# 2_viper_eagle_rep-matrix.net
KiCad netlist of a schematic drawn in Altium Designer
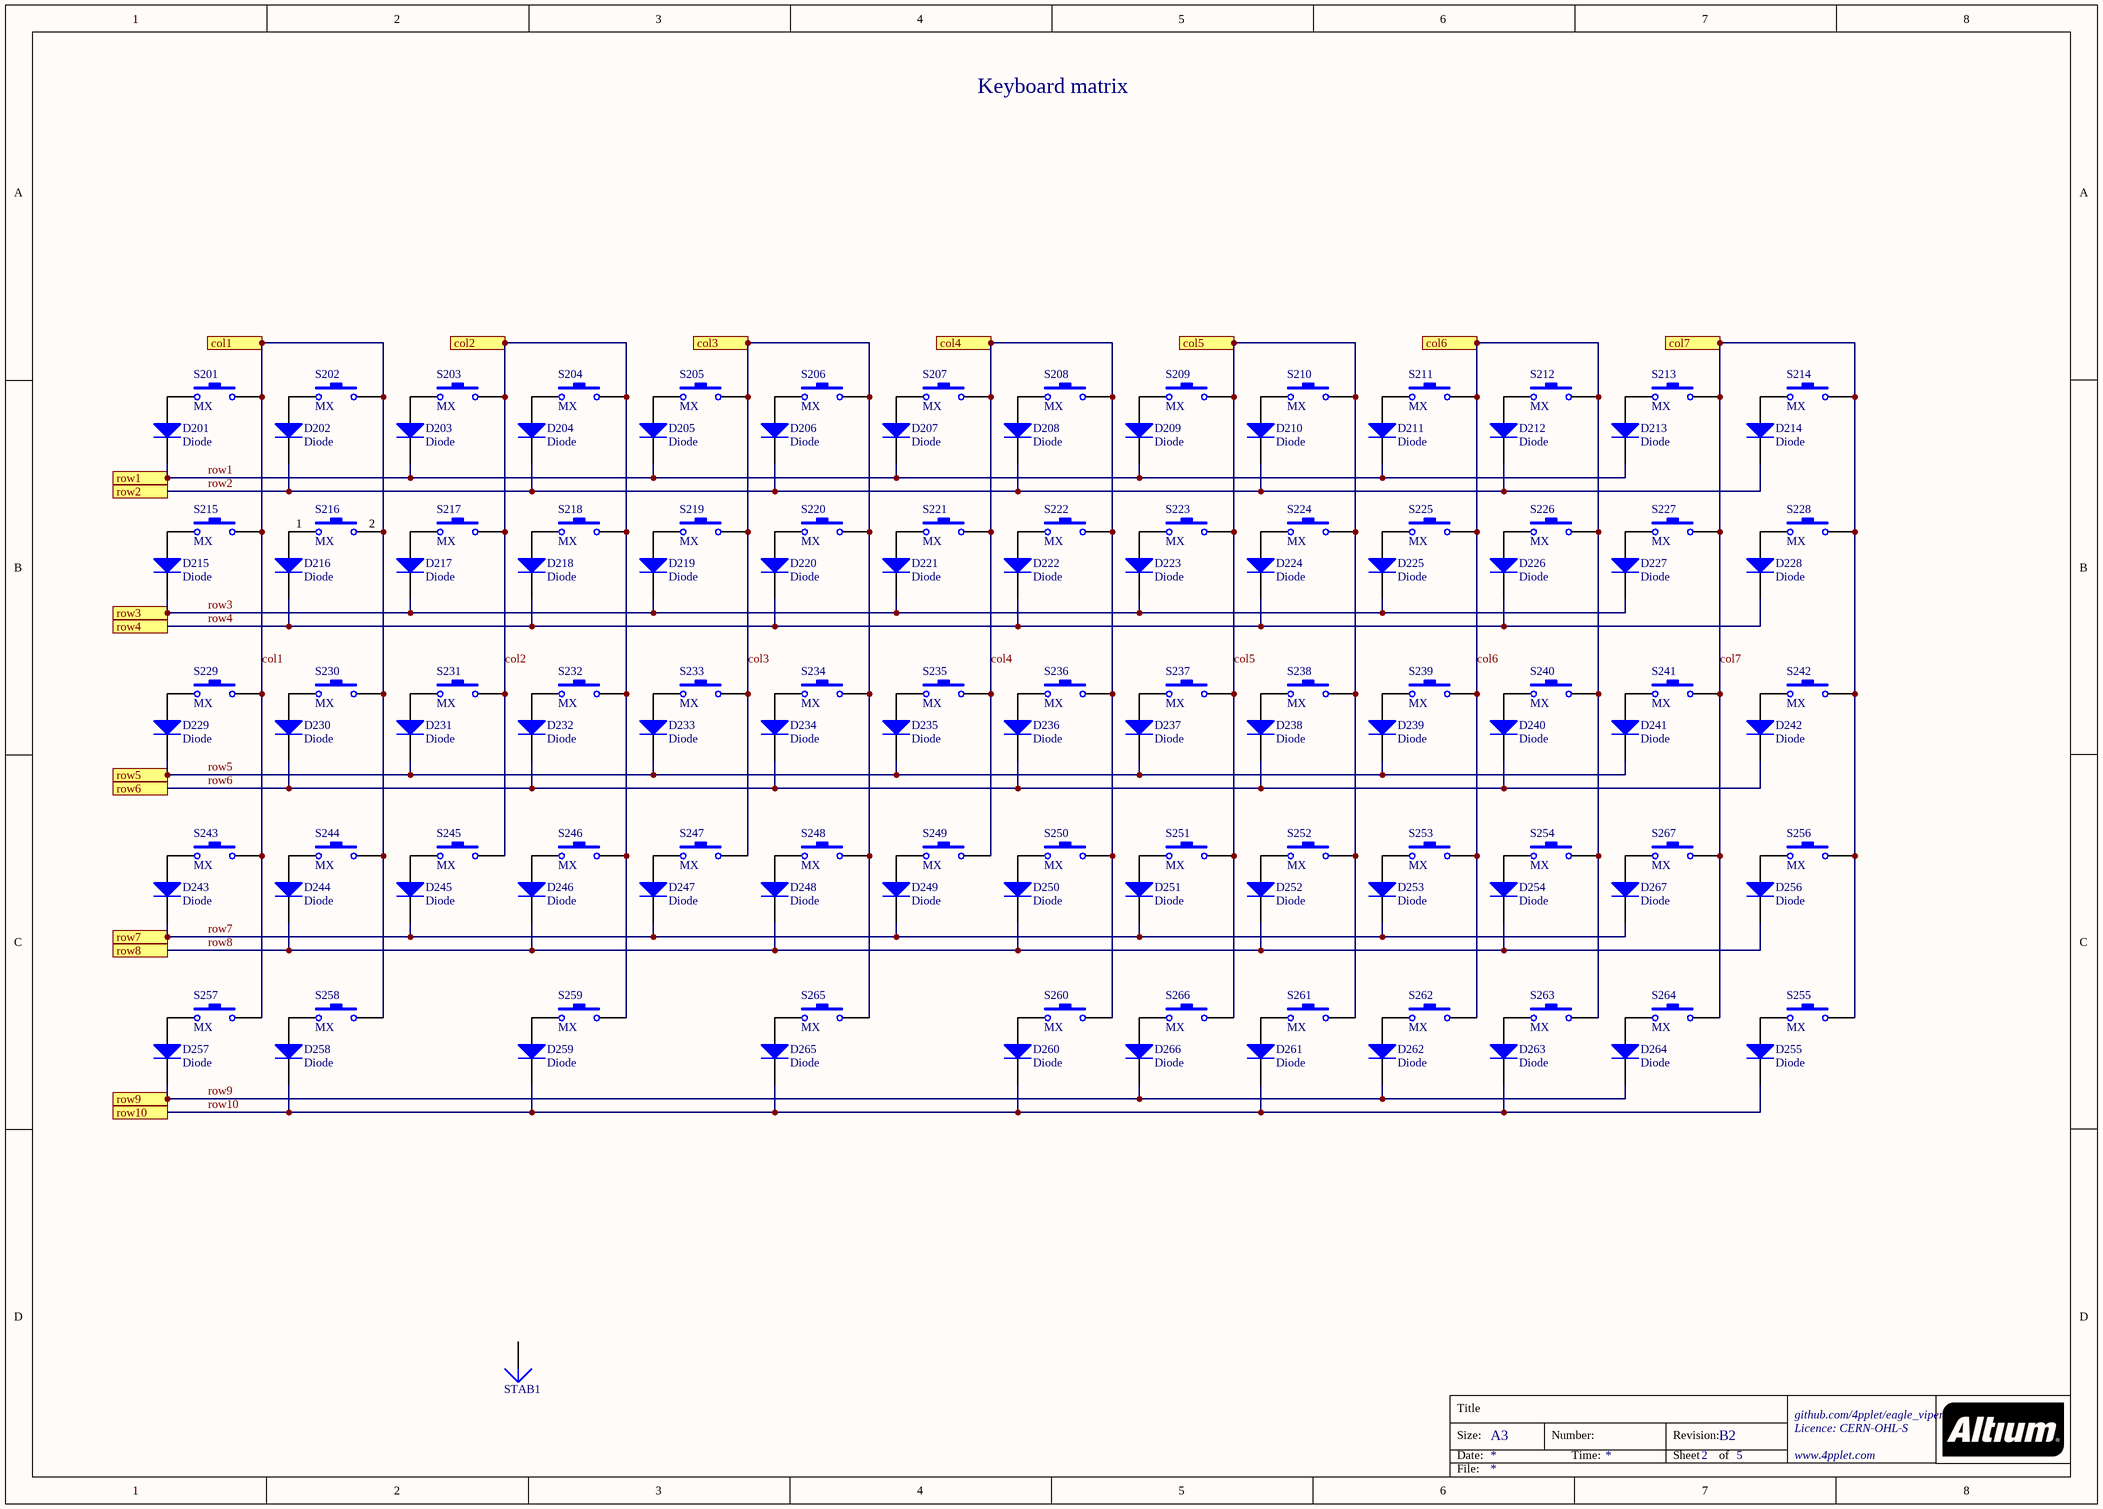
[diagram p0: 2_viper_eagle_rep-matrix.SchDoc]

(export (version "E")
  (design (tool "Eeschema 10.0.6"))
  (components
    (comp (ref "D201")
      (value "Diode")
      (footprint "SOD-123")
      (description "Default Diode")
      (fields (field (name "LCSC PART #") "C81598") (field (name "MRF.PART") "1N4148W"))
      (libsource (lib "Miscellaneous Devices") (part "Diode"))
    )
    (comp (ref "D202")
      (value "Diode")
      (footprint "SOD-123")
      (description "Default Diode")
      (fields (field (name "LCSC PART #") "C81598") (field (name "MRF.PART") "1N4148W"))
      (libsource (lib "Miscellaneous Devices") (part "Diode"))
    )
    (comp (ref "D203")
      (value "Diode")
      (footprint "SOD-123")
      (description "Default Diode")
      (fields (field (name "LCSC PART #") "C81598") (field (name "MRF.PART") "1N4148W"))
      (libsource (lib "Miscellaneous Devices") (part "Diode"))
    )
    (comp (ref "D204")
      (value "Diode")
      (footprint "SOD-123")
      (description "Default Diode")
      (fields (field (name "LCSC PART #") "C81598") (field (name "MRF.PART") "1N4148W"))
      (libsource (lib "Miscellaneous Devices") (part "Diode"))
    )
    (comp (ref "D205")
      (value "Diode")
      (footprint "SOD-123")
      (description "Default Diode")
      (fields (field (name "LCSC PART #") "C81598") (field (name "MRF.PART") "1N4148W"))
      (libsource (lib "Miscellaneous Devices") (part "Diode"))
    )
    (comp (ref "D206")
      (value "Diode")
      (footprint "SOD-123")
      (description "Default Diode")
      (fields (field (name "LCSC PART #") "C81598") (field (name "MRF.PART") "1N4148W"))
      (libsource (lib "Miscellaneous Devices") (part "Diode"))
    )
    (comp (ref "D207")
      (value "Diode")
      (footprint "SOD-123")
      (description "Default Diode")
      (fields (field (name "LCSC PART #") "C81598") (field (name "MRF.PART") "1N4148W"))
      (libsource (lib "Miscellaneous Devices") (part "Diode"))
    )
    (comp (ref "D208")
      (value "Diode")
      (footprint "SOD-123")
      (description "Default Diode")
      (fields (field (name "LCSC PART #") "C81598") (field (name "MRF.PART") "1N4148W"))
      (libsource (lib "Miscellaneous Devices") (part "Diode"))
    )
    (comp (ref "D209")
      (value "Diode")
      (footprint "SOD-123")
      (description "Default Diode")
      (fields (field (name "LCSC PART #") "C81598") (field (name "MRF.PART") "1N4148W"))
      (libsource (lib "Miscellaneous Devices") (part "Diode"))
    )
    (comp (ref "D210")
      (value "Diode")
      (footprint "SOD-123")
      (description "Default Diode")
      (fields (field (name "LCSC PART #") "C81598") (field (name "MRF.PART") "1N4148W"))
      (libsource (lib "Miscellaneous Devices") (part "Diode"))
    )
    (comp (ref "D211")
      (value "Diode")
      (footprint "SOD-123")
      (description "Default Diode")
      (fields (field (name "LCSC PART #") "C81598") (field (name "MRF.PART") "1N4148W"))
      (libsource (lib "Miscellaneous Devices") (part "Diode"))
    )
    (comp (ref "D212")
      (value "Diode")
      (footprint "SOD-123")
      (description "Default Diode")
      (fields (field (name "LCSC PART #") "C81598") (field (name "MRF.PART") "1N4148W"))
      (libsource (lib "Miscellaneous Devices") (part "Diode"))
    )
    (comp (ref "D213")
      (value "Diode")
      (footprint "SOD-123")
      (description "Default Diode")
      (fields (field (name "LCSC PART #") "C81598") (field (name "MRF.PART") "1N4148W"))
      (libsource (lib "Miscellaneous Devices") (part "Diode"))
    )
    (comp (ref "D214")
      (value "Diode")
      (footprint "SOD-123")
      (description "Default Diode")
      (fields (field (name "LCSC PART #") "C81598") (field (name "MRF.PART") "1N4148W"))
      (libsource (lib "Miscellaneous Devices") (part "Diode"))
    )
    (comp (ref "D215")
      (value "Diode")
      (footprint "SOD-123")
      (description "Default Diode")
      (fields (field (name "LCSC PART #") "C81598") (field (name "MRF.PART") "1N4148W"))
      (libsource (lib "Miscellaneous Devices") (part "Diode"))
    )
    (comp (ref "D216")
      (value "Diode")
      (footprint "SOD-123")
      (description "Default Diode")
      (fields (field (name "LCSC PART #") "C81598") (field (name "MRF.PART") "1N4148W"))
      (libsource (lib "Miscellaneous Devices") (part "Diode"))
    )
    (comp (ref "D217")
      (value "Diode")
      (footprint "SOD-123")
      (description "Default Diode")
      (fields (field (name "LCSC PART #") "C81598") (field (name "MRF.PART") "1N4148W"))
      (libsource (lib "Miscellaneous Devices") (part "Diode"))
    )
    (comp (ref "D218")
      (value "Diode")
      (footprint "SOD-123")
      (description "Default Diode")
      (fields (field (name "LCSC PART #") "C81598") (field (name "MRF.PART") "1N4148W"))
      (libsource (lib "Miscellaneous Devices") (part "Diode"))
    )
    (comp (ref "D219")
      (value "Diode")
      (footprint "SOD-123")
      (description "Default Diode")
      (fields (field (name "LCSC PART #") "C81598") (field (name "MRF.PART") "1N4148W"))
      (libsource (lib "Miscellaneous Devices") (part "Diode"))
    )
    (comp (ref "D220")
      (value "Diode")
      (footprint "SOD-123")
      (description "Default Diode")
      (fields (field (name "LCSC PART #") "C81598") (field (name "MRF.PART") "1N4148W"))
      (libsource (lib "Miscellaneous Devices") (part "Diode"))
    )
    (comp (ref "D221")
      (value "Diode")
      (footprint "SOD-123")
      (description "Default Diode")
      (fields (field (name "LCSC PART #") "C81598") (field (name "MRF.PART") "1N4148W"))
      (libsource (lib "Miscellaneous Devices") (part "Diode"))
    )
    (comp (ref "D222")
      (value "Diode")
      (footprint "SOD-123")
      (description "Default Diode")
      (fields (field (name "LCSC PART #") "C81598") (field (name "MRF.PART") "1N4148W"))
      (libsource (lib "Miscellaneous Devices") (part "Diode"))
    )
    (comp (ref "D223")
      (value "Diode")
      (footprint "SOD-123")
      (description "Default Diode")
      (fields (field (name "LCSC PART #") "C81598") (field (name "MRF.PART") "1N4148W"))
      (libsource (lib "Miscellaneous Devices") (part "Diode"))
    )
    (comp (ref "D224")
      (value "Diode")
      (footprint "SOD-123")
      (description "Default Diode")
      (fields (field (name "LCSC PART #") "C81598") (field (name "MRF.PART") "1N4148W"))
      (libsource (lib "Miscellaneous Devices") (part "Diode"))
    )
    (comp (ref "D225")
      (value "Diode")
      (footprint "SOD-123")
      (description "Default Diode")
      (fields (field (name "LCSC PART #") "C81598") (field (name "MRF.PART") "1N4148W"))
      (libsource (lib "Miscellaneous Devices") (part "Diode"))
    )
    (comp (ref "D226")
      (value "Diode")
      (footprint "SOD-123")
      (description "Default Diode")
      (fields (field (name "LCSC PART #") "C81598") (field (name "MRF.PART") "1N4148W"))
      (libsource (lib "Miscellaneous Devices") (part "Diode"))
    )
    (comp (ref "D227")
      (value "Diode")
      (footprint "SOD-123")
      (description "Default Diode")
      (fields (field (name "LCSC PART #") "C81598") (field (name "MRF.PART") "1N4148W"))
      (libsource (lib "Miscellaneous Devices") (part "Diode"))
    )
    (comp (ref "D228")
      (value "Diode")
      (footprint "SOD-123")
      (description "Default Diode")
      (fields (field (name "LCSC PART #") "C81598") (field (name "MRF.PART") "1N4148W"))
      (libsource (lib "Miscellaneous Devices") (part "Diode"))
    )
    (comp (ref "D229")
      (value "Diode")
      (footprint "SOD-123")
      (description "Default Diode")
      (fields (field (name "LCSC PART #") "C81598") (field (name "MRF.PART") "1N4148W"))
      (libsource (lib "Miscellaneous Devices") (part "Diode"))
    )
    (comp (ref "D230")
      (value "Diode")
      (footprint "SOD-123")
      (description "Default Diode")
      (fields (field (name "LCSC PART #") "C81598") (field (name "MRF.PART") "1N4148W"))
      (libsource (lib "Miscellaneous Devices") (part "Diode"))
    )
    (comp (ref "D231")
      (value "Diode")
      (footprint "SOD-123")
      (description "Default Diode")
      (fields (field (name "LCSC PART #") "C81598") (field (name "MRF.PART") "1N4148W"))
      (libsource (lib "Miscellaneous Devices") (part "Diode"))
    )
    (comp (ref "D232")
      (value "Diode")
      (footprint "SOD-123")
      (description "Default Diode")
      (fields (field (name "LCSC PART #") "C81598") (field (name "MRF.PART") "1N4148W"))
      (libsource (lib "Miscellaneous Devices") (part "Diode"))
    )
    (comp (ref "D233")
      (value "Diode")
      (footprint "SOD-123")
      (description "Default Diode")
      (fields (field (name "LCSC PART #") "C81598") (field (name "MRF.PART") "1N4148W"))
      (libsource (lib "Miscellaneous Devices") (part "Diode"))
    )
    (comp (ref "D234")
      (value "Diode")
      (footprint "SOD-123")
      (description "Default Diode")
      (fields (field (name "LCSC PART #") "C81598") (field (name "MRF.PART") "1N4148W"))
      (libsource (lib "Miscellaneous Devices") (part "Diode"))
    )
    (comp (ref "D235")
      (value "Diode")
      (footprint "SOD-123")
      (description "Default Diode")
      (fields (field (name "LCSC PART #") "C81598") (field (name "MRF.PART") "1N4148W"))
      (libsource (lib "Miscellaneous Devices") (part "Diode"))
    )
    (comp (ref "D236")
      (value "Diode")
      (footprint "SOD-123")
      (description "Default Diode")
      (fields (field (name "LCSC PART #") "C81598") (field (name "MRF.PART") "1N4148W"))
      (libsource (lib "Miscellaneous Devices") (part "Diode"))
    )
    (comp (ref "D237")
      (value "Diode")
      (footprint "SOD-123")
      (description "Default Diode")
      (fields (field (name "LCSC PART #") "C81598") (field (name "MRF.PART") "1N4148W"))
      (libsource (lib "Miscellaneous Devices") (part "Diode"))
    )
    (comp (ref "D238")
      (value "Diode")
      (footprint "SOD-123")
      (description "Default Diode")
      (fields (field (name "LCSC PART #") "C81598") (field (name "MRF.PART") "1N4148W"))
      (libsource (lib "Miscellaneous Devices") (part "Diode"))
    )
    (comp (ref "D239")
      (value "Diode")
      (footprint "SOD-123")
      (description "Default Diode")
      (fields (field (name "LCSC PART #") "C81598") (field (name "MRF.PART") "1N4148W"))
      (libsource (lib "Miscellaneous Devices") (part "Diode"))
    )
    (comp (ref "D240")
      (value "Diode")
      (footprint "SOD-123")
      (description "Default Diode")
      (fields (field (name "LCSC PART #") "C81598") (field (name "MRF.PART") "1N4148W"))
      (libsource (lib "Miscellaneous Devices") (part "Diode"))
    )
    (comp (ref "D241")
      (value "Diode")
      (footprint "SOD-123")
      (description "Default Diode")
      (fields (field (name "LCSC PART #") "C81598") (field (name "MRF.PART") "1N4148W"))
      (libsource (lib "Miscellaneous Devices") (part "Diode"))
    )
    (comp (ref "D242")
      (value "Diode")
      (footprint "SOD-123")
      (description "Default Diode")
      (fields (field (name "LCSC PART #") "C81598") (field (name "MRF.PART") "1N4148W"))
      (libsource (lib "Miscellaneous Devices") (part "Diode"))
    )
    (comp (ref "D243")
      (value "Diode")
      (footprint "SOD-123")
      (description "Default Diode")
      (fields (field (name "LCSC PART #") "C81598") (field (name "MRF.PART") "1N4148W"))
      (libsource (lib "Miscellaneous Devices") (part "Diode"))
    )
    (comp (ref "D244")
      (value "Diode")
      (footprint "SOD-123")
      (description "Default Diode")
      (fields (field (name "LCSC PART #") "C81598") (field (name "MRF.PART") "1N4148W"))
      (libsource (lib "Miscellaneous Devices") (part "Diode"))
    )
    (comp (ref "D245")
      (value "Diode")
      (footprint "SOD-123")
      (description "Default Diode")
      (fields (field (name "LCSC PART #") "C81598") (field (name "MRF.PART") "1N4148W"))
      (libsource (lib "Miscellaneous Devices") (part "Diode"))
    )
    (comp (ref "D246")
      (value "Diode")
      (footprint "SOD-123")
      (description "Default Diode")
      (fields (field (name "LCSC PART #") "C81598") (field (name "MRF.PART") "1N4148W"))
      (libsource (lib "Miscellaneous Devices") (part "Diode"))
    )
    (comp (ref "D247")
      (value "Diode")
      (footprint "SOD-123")
      (description "Default Diode")
      (fields (field (name "LCSC PART #") "C81598") (field (name "MRF.PART") "1N4148W"))
      (libsource (lib "Miscellaneous Devices") (part "Diode"))
    )
    (comp (ref "D248")
      (value "Diode")
      (footprint "SOD-123")
      (description "Default Diode")
      (fields (field (name "LCSC PART #") "C81598") (field (name "MRF.PART") "1N4148W"))
      (libsource (lib "Miscellaneous Devices") (part "Diode"))
    )
    (comp (ref "D249")
      (value "Diode")
      (footprint "SOD-123")
      (description "Default Diode")
      (fields (field (name "LCSC PART #") "C81598") (field (name "MRF.PART") "1N4148W"))
      (libsource (lib "Miscellaneous Devices") (part "Diode"))
    )
    (comp (ref "D250")
      (value "Diode")
      (footprint "SOD-123")
      (description "Default Diode")
      (fields (field (name "LCSC PART #") "C81598") (field (name "MRF.PART") "1N4148W"))
      (libsource (lib "Miscellaneous Devices") (part "Diode"))
    )
    (comp (ref "D251")
      (value "Diode")
      (footprint "SOD-123")
      (description "Default Diode")
      (fields (field (name "LCSC PART #") "C81598") (field (name "MRF.PART") "1N4148W"))
      (libsource (lib "Miscellaneous Devices") (part "Diode"))
    )
    (comp (ref "D252")
      (value "Diode")
      (footprint "SOD-123")
      (description "Default Diode")
      (fields (field (name "LCSC PART #") "C81598") (field (name "MRF.PART") "1N4148W"))
      (libsource (lib "Miscellaneous Devices") (part "Diode"))
    )
    (comp (ref "D253")
      (value "Diode")
      (footprint "SOD-123")
      (description "Default Diode")
      (fields (field (name "LCSC PART #") "C81598") (field (name "MRF.PART") "1N4148W"))
      (libsource (lib "Miscellaneous Devices") (part "Diode"))
    )
    (comp (ref "D254")
      (value "Diode")
      (footprint "SOD-123")
      (description "Default Diode")
      (fields (field (name "LCSC PART #") "C81598") (field (name "MRF.PART") "1N4148W"))
      (libsource (lib "Miscellaneous Devices") (part "Diode"))
    )
    (comp (ref "D255")
      (value "Diode")
      (footprint "SOD-123")
      (description "Default Diode")
      (fields (field (name "LCSC PART #") "C81598") (field (name "MRF.PART") "1N4148W"))
      (libsource (lib "Miscellaneous Devices") (part "Diode"))
    )
    (comp (ref "D256")
      (value "Diode")
      (footprint "SOD-123")
      (description "Default Diode")
      (fields (field (name "LCSC PART #") "C81598") (field (name "MRF.PART") "1N4148W"))
      (libsource (lib "Miscellaneous Devices") (part "Diode"))
    )
    (comp (ref "D257")
      (value "Diode")
      (footprint "SOD-123")
      (description "Default Diode")
      (fields (field (name "LCSC PART #") "C81598") (field (name "MRF.PART") "1N4148W"))
      (libsource (lib "Miscellaneous Devices") (part "Diode"))
    )
    (comp (ref "D258")
      (value "Diode")
      (footprint "SOD-123")
      (description "Default Diode")
      (fields (field (name "LCSC PART #") "C81598") (field (name "MRF.PART") "1N4148W"))
      (libsource (lib "Miscellaneous Devices") (part "Diode"))
    )
    (comp (ref "D259")
      (value "Diode")
      (footprint "SOD-123")
      (description "Default Diode")
      (fields (field (name "LCSC PART #") "C81598") (field (name "MRF.PART") "1N4148W"))
      (libsource (lib "Miscellaneous Devices") (part "Diode"))
    )
    (comp (ref "D260")
      (value "Diode")
      (footprint "SOD-123")
      (description "Default Diode")
      (fields (field (name "LCSC PART #") "C81598") (field (name "MRF.PART") "1N4148W"))
      (libsource (lib "Miscellaneous Devices") (part "Diode"))
    )
    (comp (ref "D261")
      (value "Diode")
      (footprint "SOD-123")
      (description "Default Diode")
      (fields (field (name "LCSC PART #") "C81598") (field (name "MRF.PART") "1N4148W"))
      (libsource (lib "Miscellaneous Devices") (part "Diode"))
    )
    (comp (ref "D262")
      (value "Diode")
      (footprint "SOD-123")
      (description "Default Diode")
      (fields (field (name "LCSC PART #") "C81598") (field (name "MRF.PART") "1N4148W"))
      (libsource (lib "Miscellaneous Devices") (part "Diode"))
    )
    (comp (ref "D263")
      (value "Diode")
      (footprint "SOD-123")
      (description "Default Diode")
      (fields (field (name "LCSC PART #") "C81598") (field (name "MRF.PART") "1N4148W"))
      (libsource (lib "Miscellaneous Devices") (part "Diode"))
    )
    (comp (ref "D264")
      (value "Diode")
      (footprint "SOD-123")
      (description "Default Diode")
      (fields (field (name "LCSC PART #") "C81598") (field (name "MRF.PART") "1N4148W"))
      (libsource (lib "Miscellaneous Devices") (part "Diode"))
    )
    (comp (ref "D265")
      (value "Diode")
      (footprint "SOD-123")
      (description "Default Diode")
      (fields (field (name "LCSC PART #") "C81598") (field (name "MRF.PART") "1N4148W"))
      (libsource (lib "Miscellaneous Devices") (part "Diode"))
    )
    (comp (ref "D266")
      (value "Diode")
      (footprint "SOD-123")
      (description "Default Diode")
      (fields (field (name "LCSC PART #") "C81598") (field (name "MRF.PART") "1N4148W"))
      (libsource (lib "Miscellaneous Devices") (part "Diode"))
    )
    (comp (ref "D267")
      (value "Diode")
      (footprint "SOD-123")
      (description "Default Diode")
      (fields (field (name "LCSC PART #") "C81598") (field (name "MRF.PART") "1N4148W"))
      (libsource (lib "Miscellaneous Devices") (part "Diode"))
    )
    (comp (ref "S201")
      (value "MX")
      (footprint "MX-switch - switched pol")
      (description "Switch")
      (libsource (lib "Miscellaneous Devices") (part "SW-PB"))
    )
    (comp (ref "S202")
      (value "MX")
      (footprint "MX-switch - switched pol - connector")
      (description "Switch")
      (libsource (lib "Miscellaneous Devices") (part "SW-PB"))
    )
    (comp (ref "S203")
      (value "MX")
      (footprint "MX-switch - switched pol")
      (description "Switch")
      (libsource (lib "Miscellaneous Devices") (part "SW-PB"))
    )
    (comp (ref "S204")
      (value "MX")
      (footprint "MX-switch - switched pol")
      (description "Switch")
      (libsource (lib "Miscellaneous Devices") (part "SW-PB"))
    )
    (comp (ref "S205")
      (value "MX")
      (footprint "MX-switch - switched pol")
      (description "Switch")
      (libsource (lib "Miscellaneous Devices") (part "SW-PB"))
    )
    (comp (ref "S206")
      (value "MX")
      (footprint "MX-switch - switched pol")
      (description "Switch")
      (libsource (lib "Miscellaneous Devices") (part "SW-PB"))
    )
    (comp (ref "S207")
      (value "MX")
      (footprint "MX-switch")
      (description "Switch")
      (libsource (lib "Miscellaneous Devices") (part "SW-PB"))
    )
    (comp (ref "S208")
      (value "MX")
      (footprint "MX-switch - switched pol")
      (description "Switch")
      (libsource (lib "Miscellaneous Devices") (part "SW-PB"))
    )
    (comp (ref "S209")
      (value "MX")
      (footprint "MX-switch - switched pol")
      (description "Switch")
      (libsource (lib "Miscellaneous Devices") (part "SW-PB"))
    )
    (comp (ref "S210")
      (value "MX")
      (footprint "MX-switch - switched pol")
      (description "Switch")
      (libsource (lib "Miscellaneous Devices") (part "SW-PB"))
    )
    (comp (ref "S211")
      (value "MX")
      (footprint "MX-switch - switched pol")
      (description "Switch")
      (libsource (lib "Miscellaneous Devices") (part "SW-PB"))
    )
    (comp (ref "S212")
      (value "MX")
      (footprint "MX-switch - switched pol")
      (description "Switch")
      (libsource (lib "Miscellaneous Devices") (part "SW-PB"))
    )
    (comp (ref "S213")
      (value "MX")
      (footprint "MX-switch - switched pol")
      (description "Switch")
      (libsource (lib "Miscellaneous Devices") (part "SW-PB"))
    )
    (comp (ref "S214")
      (value "MX")
      (footprint "MX-switch")
      (description "Switch")
      (libsource (lib "Miscellaneous Devices") (part "SW-PB"))
    )
    (comp (ref "S215")
      (value "MX")
      (footprint "MX-switch - 1.5U")
      (description "TAB")
      (libsource (lib "Miscellaneous Devices") (part "SW-PB"))
    )
    (comp (ref "S216")
      (value "MX")
      (footprint "MX-switch - switched pol")
      (description "Switch")
      (libsource (lib "") (part "SW-PB_1"))
    )
    (comp (ref "S217")
      (value "MX")
      (footprint "MX-switch - switched pol")
      (description "Switch")
      (libsource (lib "Miscellaneous Devices") (part "SW-PB"))
    )
    (comp (ref "S218")
      (value "MX")
      (footprint "MX-switch - switched pol")
      (description "Switch")
      (libsource (lib "Miscellaneous Devices") (part "SW-PB"))
    )
    (comp (ref "S219")
      (value "MX")
      (footprint "MX-switch - switched pol")
      (description "Switch")
      (libsource (lib "Miscellaneous Devices") (part "SW-PB"))
    )
    (comp (ref "S220")
      (value "MX")
      (footprint "MX-switch")
      (description "Switch")
      (libsource (lib "Miscellaneous Devices") (part "SW-PB"))
    )
    (comp (ref "S221")
      (value "MX")
      (footprint "MX-switch - switched pol")
      (description "Switch")
      (libsource (lib "Miscellaneous Devices") (part "SW-PB"))
    )
    (comp (ref "S222")
      (value "MX")
      (footprint "MX-switch - switched pol")
      (description "Switch")
      (libsource (lib "Miscellaneous Devices") (part "SW-PB"))
    )
    (comp (ref "S223")
      (value "MX")
      (footprint "MX-switch - switched pol")
      (description "Switch")
      (libsource (lib "Miscellaneous Devices") (part "SW-PB"))
    )
    (comp (ref "S224")
      (value "MX")
      (footprint "MX-switch - switched pol")
      (description "Switch")
      (libsource (lib "Miscellaneous Devices") (part "SW-PB"))
    )
    (comp (ref "S225")
      (value "MX")
      (footprint "MX-switch - switched pol")
      (description "Switch")
      (libsource (lib "Miscellaneous Devices") (part "SW-PB"))
    )
    (comp (ref "S226")
      (value "MX")
      (footprint "MX-switch")
      (description "Switch")
      (libsource (lib "Miscellaneous Devices") (part "SW-PB"))
    )
    (comp (ref "S227")
      (value "MX")
      (footprint "MX-switch - switched pol")
      (description "Switch")
      (libsource (lib "Miscellaneous Devices") (part "SW-PB"))
    )
    (comp (ref "S228")
      (value "MX")
      (footprint "MX-switch - backspace")
      (description "Switch")
      (libsource (lib "Miscellaneous Devices") (part "SW-PB"))
    )
    (comp (ref "S229")
      (value "MX")
      (footprint "MX-switch - CAPS")
      (description "Switch")
      (libsource (lib "Miscellaneous Devices") (part "SW-PB"))
    )
    (comp (ref "S230")
      (value "MX")
      (footprint "MX-switch - switched pol")
      (description "Switch")
      (libsource (lib "Miscellaneous Devices") (part "SW-PB"))
    )
    (comp (ref "S231")
      (value "MX")
      (footprint "MX-switch - switched pol")
      (description "Switch")
      (libsource (lib "Miscellaneous Devices") (part "SW-PB"))
    )
    (comp (ref "S232")
      (value "MX")
      (footprint "MX-switch - switched pol")
      (description "Switch")
      (libsource (lib "Miscellaneous Devices") (part "SW-PB"))
    )
    (comp (ref "S233")
      (value "MX")
      (footprint "MX-switch - switched pol")
      (description "Switch")
      (libsource (lib "Miscellaneous Devices") (part "SW-PB"))
    )
    (comp (ref "S234")
      (value "MX")
      (footprint "MX-switch - switched pol")
      (description "Switch")
      (libsource (lib "Miscellaneous Devices") (part "SW-PB"))
    )
    (comp (ref "S235")
      (value "MX")
      (footprint "MX-switch - switched pol")
      (description "Switch")
      (libsource (lib "Miscellaneous Devices") (part "SW-PB"))
    )
    (comp (ref "S236")
      (value "MX")
      (footprint "MX-switch - switched pol")
      (description "Switch")
      (libsource (lib "Miscellaneous Devices") (part "SW-PB"))
    )
    (comp (ref "S237")
      (value "MX")
      (footprint "MX-switch - switched pol")
      (description "Switch")
      (libsource (lib "Miscellaneous Devices") (part "SW-PB"))
    )
    (comp (ref "S238")
      (value "MX")
      (footprint "MX-switch - switched pol")
      (description "Switch")
      (libsource (lib "Miscellaneous Devices") (part "SW-PB"))
    )
    (comp (ref "S239")
      (value "MX")
      (footprint "MX-switch")
      (description "Switch")
      (libsource (lib "Miscellaneous Devices") (part "SW-PB"))
    )
    (comp (ref "S240")
      (value "MX")
      (footprint "MX-switch - switched pol")
      (description "Switch")
      (libsource (lib "Miscellaneous Devices") (part "SW-PB"))
    )
    (comp (ref "S241")
      (value "MX")
      (footprint "MX-switch")
      (description "Switch")
      (libsource (lib "Miscellaneous Devices") (part "SW-PB"))
    )
    (comp (ref "S242")
      (value "MX")
      (footprint "MX-switch - 1.5U")
      (description "Switch")
      (libsource (lib "Miscellaneous Devices") (part "SW-PB"))
    )
    (comp (ref "S243")
      (value "MX")
      (footprint "MX-switch - Left shift")
      (description "Switch")
      (libsource (lib "Miscellaneous Devices") (part "SW-PB"))
    )
    (comp (ref "S244")
      (value "MX")
      (footprint "MX-switch")
      (description "Switch")
      (libsource (lib "Miscellaneous Devices") (part "SW-PB"))
    )
    (comp (ref "S245")
      (value "MX")
      (footprint "MX-switch - switched pol")
      (description "Switch")
      (libsource (lib "Miscellaneous Devices") (part "SW-PB"))
    )
    (comp (ref "S246")
      (value "MX")
      (footprint "MX-switch - switched pol")
      (description "Switch")
      (libsource (lib "Miscellaneous Devices") (part "SW-PB"))
    )
    (comp (ref "S247")
      (value "MX")
      (footprint "MX-switch - switched pol")
      (description "Switch")
      (libsource (lib "Miscellaneous Devices") (part "SW-PB"))
    )
    (comp (ref "S248")
      (value "MX")
      (footprint "MX-switch - switched pol")
      (description "Switch")
      (libsource (lib "Miscellaneous Devices") (part "SW-PB"))
    )
    (comp (ref "S249")
      (value "MX")
      (footprint "MX-switch - switched pol")
      (description "Switch")
      (libsource (lib "Miscellaneous Devices") (part "SW-PB"))
    )
    (comp (ref "S250")
      (value "MX")
      (footprint "MX-switch - switched pol")
      (description "Switch")
      (libsource (lib "Miscellaneous Devices") (part "SW-PB"))
    )
    (comp (ref "S251")
      (value "MX")
      (footprint "MX-switch - switched pol")
      (description "Switch")
      (libsource (lib "Miscellaneous Devices") (part "SW-PB"))
    )
    (comp (ref "S252")
      (value "MX")
      (footprint "MX-switch - switched pol")
      (description "Switch")
      (libsource (lib "Miscellaneous Devices") (part "SW-PB"))
    )
    (comp (ref "S253")
      (value "MX")
      (footprint "MX-switch - switched pol")
      (description "Switch")
      (libsource (lib "Miscellaneous Devices") (part "SW-PB"))
    )
    (comp (ref "S254")
      (value "MX")
      (footprint "MX-switch - switched pol")
      (description "Switch")
      (libsource (lib "Miscellaneous Devices") (part "SW-PB"))
    )
    (comp (ref "S255")
      (value "MX")
      (footprint "MX-switch")
      (description "Switch")
      (libsource (lib "Miscellaneous Devices") (part "SW-PB"))
    )
    (comp (ref "S256")
      (value "MX")
      (footprint "MX-switch - Enter - rotated ISO")
      (description "Switch")
      (libsource (lib "Miscellaneous Devices") (part "SW-PB"))
    )
    (comp (ref "S257")
      (value "MX")
      (footprint "MX-switch - 1.5u MOD-L")
      (description "Switch")
      (libsource (lib "Miscellaneous Devices") (part "SW-PB"))
    )
    (comp (ref "S258")
      (value "MX")
      (footprint "MX-switch - 1u MOD-L")
      (description "Switch")
      (libsource (lib "Miscellaneous Devices") (part "SW-PB"))
    )
    (comp (ref "S259")
      (value "MX")
      (footprint "MX-switch - 1.5u MOD-L")
      (description "Switch")
      (libsource (lib "Miscellaneous Devices") (part "SW-PB"))
    )
    (comp (ref "S260")
      (value "MX")
      (footprint "MX-switch - Space_V2")
      (description "Switch")
      (libsource (lib "Miscellaneous Devices") (part "SW-PB"))
    )
    (comp (ref "S261")
      (value "MX")
      (footprint "MX-switch")
      (description "Switch")
      (libsource (lib "Miscellaneous Devices") (part "SW-PB"))
    )
    (comp (ref "S262")
      (value "MX")
      (footprint "MX-switch - 1.5u MOD-R")
      (description "Switch")
      (libsource (lib "Miscellaneous Devices") (part "SW-PB"))
    )
    (comp (ref "S263")
      (value "MX")
      (footprint "MX-switch - 1u MOD-R")
      (description "Switch")
      (libsource (lib "Miscellaneous Devices") (part "SW-PB"))
    )
    (comp (ref "S264")
      (value "MX")
      (footprint "MX-switch - 1.5u MOD-R")
      (description "Switch")
      (libsource (lib "Miscellaneous Devices") (part "SW-PB"))
    )
    (comp (ref "S265")
      (value "MX")
      (footprint "MX-switch - 3U - rotated stab")
      (description "Switch")
      (libsource (lib "Miscellaneous Devices") (part "SW-PB"))
    )
    (comp (ref "S266")
      (value "MX")
      (footprint "MX-switch - 3U - rotated stab")
      (description "Switch")
      (libsource (lib "Miscellaneous Devices") (part "SW-PB"))
    )
    (comp (ref "S267")
      (value "MX")
      (footprint "MX-switch - right shift - rotated stab")
      (description "Switch")
      (libsource (lib "Miscellaneous Devices") (part "SW-PB"))
    )
    (comp (ref "STAB1")
      (value "Plug")
      (footprint "Stab 10U")
      (libsource (lib "Miscellaneous Connectors") (part "Plug"))
    )
  )
  (nets
    (net (code "1") (name "/col1") (class "Default")
      (node (ref "S201") (pin "2") (pinfunction "2_2") (pintype "passive"))
      (node (ref "S202") (pin "2") (pinfunction "2_2") (pintype "passive"))
      (node (ref "S215") (pin "1") (pinfunction "1_1") (pintype "passive"))
      (node (ref "S216") (pin "2") (pinfunction "2_2") (pintype "passive"))
      (node (ref "S229") (pin "2") (pinfunction "2_2") (pintype "passive"))
      (node (ref "S230") (pin "2") (pinfunction "2_2") (pintype "passive"))
      (node (ref "S243") (pin "2") (pinfunction "2_2") (pintype "passive"))
      (node (ref "S244") (pin "2") (pinfunction "2_2") (pintype "passive"))
      (node (ref "S257") (pin "1") (pinfunction "1_1") (pintype "passive"))
      (node (ref "S258") (pin "2") (pinfunction "2_2") (pintype "passive"))
    )
    (net (code "2") (name "/col2") (class "Default")
      (node (ref "S203") (pin "2") (pinfunction "2_2") (pintype "passive"))
      (node (ref "S204") (pin "2") (pinfunction "2_2") (pintype "passive"))
      (node (ref "S217") (pin "2") (pinfunction "2_2") (pintype "passive"))
      (node (ref "S218") (pin "2") (pinfunction "2_2") (pintype "passive"))
      (node (ref "S231") (pin "2") (pinfunction "2_2") (pintype "passive"))
      (node (ref "S232") (pin "2") (pinfunction "2_2") (pintype "passive"))
      (node (ref "S245") (pin "2") (pinfunction "2_2") (pintype "passive"))
      (node (ref "S246") (pin "2") (pinfunction "2_2") (pintype "passive"))
      (node (ref "S259") (pin "1") (pinfunction "1_1") (pintype "passive"))
    )
    (net (code "3") (name "/col3") (class "Default")
      (node (ref "S205") (pin "2") (pinfunction "2_2") (pintype "passive"))
      (node (ref "S206") (pin "2") (pinfunction "2_2") (pintype "passive"))
      (node (ref "S219") (pin "2") (pinfunction "2_2") (pintype "passive"))
      (node (ref "S220") (pin "2") (pinfunction "2_2") (pintype "passive"))
      (node (ref "S233") (pin "2") (pinfunction "2_2") (pintype "passive"))
      (node (ref "S234") (pin "2") (pinfunction "2_2") (pintype "passive"))
      (node (ref "S247") (pin "2") (pinfunction "2_2") (pintype "passive"))
      (node (ref "S248") (pin "2") (pinfunction "2_2") (pintype "passive"))
      (node (ref "S265") (pin "2") (pinfunction "2_2") (pintype "passive"))
    )
    (net (code "4") (name "/col4") (class "Default")
      (node (ref "S207") (pin "2") (pinfunction "2_2") (pintype "passive"))
      (node (ref "S208") (pin "2") (pinfunction "2_2") (pintype "passive"))
      (node (ref "S221") (pin "2") (pinfunction "2_2") (pintype "passive"))
      (node (ref "S222") (pin "2") (pinfunction "2_2") (pintype "passive"))
      (node (ref "S235") (pin "2") (pinfunction "2_2") (pintype "passive"))
      (node (ref "S236") (pin "2") (pinfunction "2_2") (pintype "passive"))
      (node (ref "S249") (pin "2") (pinfunction "2_2") (pintype "passive"))
      (node (ref "S250") (pin "2") (pinfunction "2_2") (pintype "passive"))
      (node (ref "S260") (pin "1") (pinfunction "1_1") (pintype "passive"))
    )
    (net (code "5") (name "/col5") (class "Default")
      (node (ref "S209") (pin "2") (pinfunction "2_2") (pintype "passive"))
      (node (ref "S210") (pin "2") (pinfunction "2_2") (pintype "passive"))
      (node (ref "S223") (pin "2") (pinfunction "2_2") (pintype "passive"))
      (node (ref "S224") (pin "2") (pinfunction "2_2") (pintype "passive"))
      (node (ref "S237") (pin "2") (pinfunction "2_2") (pintype "passive"))
      (node (ref "S238") (pin "2") (pinfunction "2_2") (pintype "passive"))
      (node (ref "S251") (pin "2") (pinfunction "2_2") (pintype "passive"))
      (node (ref "S252") (pin "2") (pinfunction "2_2") (pintype "passive"))
      (node (ref "S261") (pin "2") (pinfunction "2_2") (pintype "passive"))
      (node (ref "S266") (pin "2") (pinfunction "2_2") (pintype "passive"))
    )
    (net (code "6") (name "/col6") (class "Default")
      (node (ref "S211") (pin "2") (pinfunction "2_2") (pintype "passive"))
      (node (ref "S212") (pin "2") (pinfunction "2_2") (pintype "passive"))
      (node (ref "S225") (pin "2") (pinfunction "2_2") (pintype "passive"))
      (node (ref "S226") (pin "2") (pinfunction "2_2") (pintype "passive"))
      (node (ref "S239") (pin "2") (pinfunction "2_2") (pintype "passive"))
      (node (ref "S240") (pin "2") (pinfunction "2_2") (pintype "passive"))
      (node (ref "S253") (pin "2") (pinfunction "2_2") (pintype "passive"))
      (node (ref "S254") (pin "2") (pinfunction "2_2") (pintype "passive"))
      (node (ref "S262") (pin "1") (pinfunction "1_1") (pintype "passive"))
      (node (ref "S263") (pin "1") (pinfunction "1_1") (pintype "passive"))
    )
    (net (code "7") (name "/col7") (class "Default")
      (node (ref "S213") (pin "2") (pinfunction "2_2") (pintype "passive"))
      (node (ref "S214") (pin "2") (pinfunction "2_2") (pintype "passive"))
      (node (ref "S227") (pin "2") (pinfunction "2_2") (pintype "passive"))
      (node (ref "S228") (pin "1") (pinfunction "1_1") (pintype "passive"))
      (node (ref "S241") (pin "2") (pinfunction "2_2") (pintype "passive"))
      (node (ref "S242") (pin "2") (pinfunction "2_2") (pintype "passive"))
      (node (ref "S255") (pin "2") (pinfunction "2_2") (pintype "passive"))
      (node (ref "S256") (pin "2") (pinfunction "2_2") (pintype "passive"))
      (node (ref "S264") (pin "2") (pinfunction "2_2") (pintype "passive"))
      (node (ref "S267") (pin "2") (pinfunction "2_2") (pintype "passive"))
    )
    (net (code "8") (name "/row1") (class "Default")
      (node (ref "D201") (pin "2") (pinfunction "K_2") (pintype "passive"))
      (node (ref "D203") (pin "2") (pinfunction "K_2") (pintype "passive"))
      (node (ref "D205") (pin "2") (pinfunction "K_2") (pintype "passive"))
      (node (ref "D207") (pin "2") (pinfunction "K_2") (pintype "passive"))
      (node (ref "D209") (pin "2") (pinfunction "K_2") (pintype "passive"))
      (node (ref "D211") (pin "2") (pinfunction "K_2") (pintype "passive"))
      (node (ref "D213") (pin "2") (pinfunction "K_2") (pintype "passive"))
    )
    (net (code "9") (name "/row2") (class "Default")
      (node (ref "D202") (pin "2") (pinfunction "K_2") (pintype "passive"))
      (node (ref "D204") (pin "2") (pinfunction "K_2") (pintype "passive"))
      (node (ref "D206") (pin "2") (pinfunction "K_2") (pintype "passive"))
      (node (ref "D208") (pin "2") (pinfunction "K_2") (pintype "passive"))
      (node (ref "D210") (pin "2") (pinfunction "K_2") (pintype "passive"))
      (node (ref "D212") (pin "2") (pinfunction "K_2") (pintype "passive"))
      (node (ref "D214") (pin "2") (pinfunction "K_2") (pintype "passive"))
    )
    (net (code "10") (name "/row3") (class "Default")
      (node (ref "D215") (pin "2") (pinfunction "K_2") (pintype "passive"))
      (node (ref "D217") (pin "2") (pinfunction "K_2") (pintype "passive"))
      (node (ref "D219") (pin "2") (pinfunction "K_2") (pintype "passive"))
      (node (ref "D221") (pin "2") (pinfunction "K_2") (pintype "passive"))
      (node (ref "D223") (pin "2") (pinfunction "K_2") (pintype "passive"))
      (node (ref "D225") (pin "2") (pinfunction "K_2") (pintype "passive"))
      (node (ref "D227") (pin "2") (pinfunction "K_2") (pintype "passive"))
    )
    (net (code "11") (name "/row4") (class "Default")
      (node (ref "D216") (pin "2") (pinfunction "K_2") (pintype "passive"))
      (node (ref "D218") (pin "2") (pinfunction "K_2") (pintype "passive"))
      (node (ref "D220") (pin "2") (pinfunction "K_2") (pintype "passive"))
      (node (ref "D222") (pin "2") (pinfunction "K_2") (pintype "passive"))
      (node (ref "D224") (pin "2") (pinfunction "K_2") (pintype "passive"))
      (node (ref "D226") (pin "2") (pinfunction "K_2") (pintype "passive"))
      (node (ref "D228") (pin "2") (pinfunction "K_2") (pintype "passive"))
    )
    (net (code "12") (name "/row5") (class "Default")
      (node (ref "D229") (pin "2") (pinfunction "K_2") (pintype "passive"))
      (node (ref "D231") (pin "2") (pinfunction "K_2") (pintype "passive"))
      (node (ref "D233") (pin "2") (pinfunction "K_2") (pintype "passive"))
      (node (ref "D235") (pin "2") (pinfunction "K_2") (pintype "passive"))
      (node (ref "D237") (pin "2") (pinfunction "K_2") (pintype "passive"))
      (node (ref "D239") (pin "2") (pinfunction "K_2") (pintype "passive"))
      (node (ref "D241") (pin "2") (pinfunction "K_2") (pintype "passive"))
    )
    (net (code "13") (name "/row6") (class "Default")
      (node (ref "D230") (pin "2") (pinfunction "K_2") (pintype "passive"))
      (node (ref "D232") (pin "2") (pinfunction "K_2") (pintype "passive"))
      (node (ref "D234") (pin "2") (pinfunction "K_2") (pintype "passive"))
      (node (ref "D236") (pin "2") (pinfunction "K_2") (pintype "passive"))
      (node (ref "D238") (pin "2") (pinfunction "K_2") (pintype "passive"))
      (node (ref "D240") (pin "2") (pinfunction "K_2") (pintype "passive"))
      (node (ref "D242") (pin "2") (pinfunction "K_2") (pintype "passive"))
    )
    (net (code "14") (name "/row7") (class "Default")
      (node (ref "D243") (pin "2") (pinfunction "K_2") (pintype "passive"))
      (node (ref "D245") (pin "2") (pinfunction "K_2") (pintype "passive"))
      (node (ref "D247") (pin "2") (pinfunction "K_2") (pintype "passive"))
      (node (ref "D249") (pin "2") (pinfunction "K_2") (pintype "passive"))
      (node (ref "D251") (pin "2") (pinfunction "K_2") (pintype "passive"))
      (node (ref "D253") (pin "2") (pinfunction "K_2") (pintype "passive"))
      (node (ref "D267") (pin "2") (pinfunction "K_2") (pintype "passive"))
    )
    (net (code "15") (name "/row8") (class "Default")
      (node (ref "D244") (pin "2") (pinfunction "K_2") (pintype "passive"))
      (node (ref "D246") (pin "2") (pinfunction "K_2") (pintype "passive"))
      (node (ref "D248") (pin "2") (pinfunction "K_2") (pintype "passive"))
      (node (ref "D250") (pin "2") (pinfunction "K_2") (pintype "passive"))
      (node (ref "D252") (pin "2") (pinfunction "K_2") (pintype "passive"))
      (node (ref "D254") (pin "2") (pinfunction "K_2") (pintype "passive"))
      (node (ref "D256") (pin "2") (pinfunction "K_2") (pintype "passive"))
    )
    (net (code "16") (name "/row9") (class "Default")
      (node (ref "D257") (pin "2") (pinfunction "K_2") (pintype "passive"))
      (node (ref "D262") (pin "2") (pinfunction "K_2") (pintype "passive"))
      (node (ref "D264") (pin "2") (pinfunction "K_2") (pintype "passive"))
      (node (ref "D266") (pin "2") (pinfunction "K_2") (pintype "passive"))
    )
    (net (code "17") (name "/row10") (class "Default")
      (node (ref "D255") (pin "2") (pinfunction "K_2") (pintype "passive"))
      (node (ref "D258") (pin "2") (pinfunction "K_2") (pintype "passive"))
      (node (ref "D259") (pin "2") (pinfunction "K_2") (pintype "passive"))
      (node (ref "D260") (pin "2") (pinfunction "K_2") (pintype "passive"))
      (node (ref "D261") (pin "2") (pinfunction "K_2") (pintype "passive"))
      (node (ref "D263") (pin "2") (pinfunction "K_2") (pintype "passive"))
      (node (ref "D265") (pin "2") (pinfunction "K_2") (pintype "passive"))
    )
    (net (code "18") (name "Net-(D201-A)") (class "Default")
      (node (ref "D201") (pin "1") (pinfunction "A_1") (pintype "passive"))
      (node (ref "S201") (pin "1") (pinfunction "1_1") (pintype "passive"))
    )
    (net (code "19") (name "Net-(D202-A)") (class "Default")
      (node (ref "D202") (pin "1") (pinfunction "A_1") (pintype "passive"))
      (node (ref "S202") (pin "1") (pinfunction "1_1") (pintype "passive"))
    )
    (net (code "20") (name "Net-(D203-A)") (class "Default")
      (node (ref "D203") (pin "1") (pinfunction "A_1") (pintype "passive"))
      (node (ref "S203") (pin "1") (pinfunction "1_1") (pintype "passive"))
    )
    (net (code "21") (name "Net-(D204-A)") (class "Default")
      (node (ref "D204") (pin "1") (pinfunction "A_1") (pintype "passive"))
      (node (ref "S204") (pin "1") (pinfunction "1_1") (pintype "passive"))
    )
    (net (code "22") (name "Net-(D205-A)") (class "Default")
      (node (ref "D205") (pin "1") (pinfunction "A_1") (pintype "passive"))
      (node (ref "S205") (pin "1") (pinfunction "1_1") (pintype "passive"))
    )
    (net (code "23") (name "Net-(D206-A)") (class "Default")
      (node (ref "D206") (pin "1") (pinfunction "A_1") (pintype "passive"))
      (node (ref "S206") (pin "1") (pinfunction "1_1") (pintype "passive"))
    )
    (net (code "24") (name "Net-(D207-A)") (class "Default")
      (node (ref "D207") (pin "1") (pinfunction "A_1") (pintype "passive"))
      (node (ref "S207") (pin "1") (pinfunction "1_1") (pintype "passive"))
    )
    (net (code "25") (name "Net-(D208-A)") (class "Default")
      (node (ref "D208") (pin "1") (pinfunction "A_1") (pintype "passive"))
      (node (ref "S208") (pin "1") (pinfunction "1_1") (pintype "passive"))
    )
    (net (code "26") (name "Net-(D209-A)") (class "Default")
      (node (ref "D209") (pin "1") (pinfunction "A_1") (pintype "passive"))
      (node (ref "S209") (pin "1") (pinfunction "1_1") (pintype "passive"))
    )
    (net (code "27") (name "Net-(D210-A)") (class "Default")
      (node (ref "D210") (pin "1") (pinfunction "A_1") (pintype "passive"))
      (node (ref "S210") (pin "1") (pinfunction "1_1") (pintype "passive"))
    )
    (net (code "28") (name "Net-(D211-A)") (class "Default")
      (node (ref "D211") (pin "1") (pinfunction "A_1") (pintype "passive"))
      (node (ref "S211") (pin "1") (pinfunction "1_1") (pintype "passive"))
    )
    (net (code "29") (name "Net-(D212-A)") (class "Default")
      (node (ref "D212") (pin "1") (pinfunction "A_1") (pintype "passive"))
      (node (ref "S212") (pin "1") (pinfunction "1_1") (pintype "passive"))
    )
    (net (code "30") (name "Net-(D213-A)") (class "Default")
      (node (ref "D213") (pin "1") (pinfunction "A_1") (pintype "passive"))
      (node (ref "S213") (pin "1") (pinfunction "1_1") (pintype "passive"))
    )
    (net (code "31") (name "Net-(D214-A)") (class "Default")
      (node (ref "D214") (pin "1") (pinfunction "A_1") (pintype "passive"))
      (node (ref "S214") (pin "1") (pinfunction "1_1") (pintype "passive"))
    )
    (net (code "32") (name "Net-(D215-A)") (class "Default")
      (node (ref "D215") (pin "1") (pinfunction "A_1") (pintype "passive"))
      (node (ref "S215") (pin "2") (pinfunction "2_2") (pintype "passive"))
    )
    (net (code "33") (name "Net-(D216-A)") (class "Default")
      (node (ref "D216") (pin "1") (pinfunction "A_1") (pintype "passive"))
      (node (ref "S216") (pin "1") (pinfunction "1_1") (pintype "passive"))
    )
    (net (code "34") (name "Net-(D217-A)") (class "Default")
      (node (ref "D217") (pin "1") (pinfunction "A_1") (pintype "passive"))
      (node (ref "S217") (pin "1") (pinfunction "1_1") (pintype "passive"))
    )
    (net (code "35") (name "Net-(D218-A)") (class "Default")
      (node (ref "D218") (pin "1") (pinfunction "A_1") (pintype "passive"))
      (node (ref "S218") (pin "1") (pinfunction "1_1") (pintype "passive"))
    )
    (net (code "36") (name "Net-(D219-A)") (class "Default")
      (node (ref "D219") (pin "1") (pinfunction "A_1") (pintype "passive"))
      (node (ref "S219") (pin "1") (pinfunction "1_1") (pintype "passive"))
    )
    (net (code "37") (name "Net-(D220-A)") (class "Default")
      (node (ref "D220") (pin "1") (pinfunction "A_1") (pintype "passive"))
      (node (ref "S220") (pin "1") (pinfunction "1_1") (pintype "passive"))
    )
    (net (code "38") (name "Net-(D221-A)") (class "Default")
      (node (ref "D221") (pin "1") (pinfunction "A_1") (pintype "passive"))
      (node (ref "S221") (pin "1") (pinfunction "1_1") (pintype "passive"))
    )
    (net (code "39") (name "Net-(D222-A)") (class "Default")
      (node (ref "D222") (pin "1") (pinfunction "A_1") (pintype "passive"))
      (node (ref "S222") (pin "1") (pinfunction "1_1") (pintype "passive"))
    )
    (net (code "40") (name "Net-(D223-A)") (class "Default")
      (node (ref "D223") (pin "1") (pinfunction "A_1") (pintype "passive"))
      (node (ref "S223") (pin "1") (pinfunction "1_1") (pintype "passive"))
    )
    (net (code "41") (name "Net-(D224-A)") (class "Default")
      (node (ref "D224") (pin "1") (pinfunction "A_1") (pintype "passive"))
      (node (ref "S224") (pin "1") (pinfunction "1_1") (pintype "passive"))
    )
    (net (code "42") (name "Net-(D225-A)") (class "Default")
      (node (ref "D225") (pin "1") (pinfunction "A_1") (pintype "passive"))
      (node (ref "S225") (pin "1") (pinfunction "1_1") (pintype "passive"))
    )
    (net (code "43") (name "Net-(D226-A)") (class "Default")
      (node (ref "D226") (pin "1") (pinfunction "A_1") (pintype "passive"))
      (node (ref "S226") (pin "1") (pinfunction "1_1") (pintype "passive"))
    )
    (net (code "44") (name "Net-(D227-A)") (class "Default")
      (node (ref "D227") (pin "1") (pinfunction "A_1") (pintype "passive"))
      (node (ref "S227") (pin "1") (pinfunction "1_1") (pintype "passive"))
    )
    (net (code "45") (name "Net-(D228-A)") (class "Default")
      (node (ref "D228") (pin "1") (pinfunction "A_1") (pintype "passive"))
      (node (ref "S228") (pin "2") (pinfunction "2_2") (pintype "passive"))
    )
    (net (code "46") (name "Net-(D229-A)") (class "Default")
      (node (ref "D229") (pin "1") (pinfunction "A_1") (pintype "passive"))
      (node (ref "S229") (pin "1") (pinfunction "1_1") (pintype "passive"))
    )
    (net (code "47") (name "Net-(D230-A)") (class "Default")
      (node (ref "D230") (pin "1") (pinfunction "A_1") (pintype "passive"))
      (node (ref "S230") (pin "1") (pinfunction "1_1") (pintype "passive"))
    )
    (net (code "48") (name "Net-(D231-A)") (class "Default")
      (node (ref "D231") (pin "1") (pinfunction "A_1") (pintype "passive"))
      (node (ref "S231") (pin "1") (pinfunction "1_1") (pintype "passive"))
    )
    (net (code "49") (name "Net-(D232-A)") (class "Default")
      (node (ref "D232") (pin "1") (pinfunction "A_1") (pintype "passive"))
      (node (ref "S232") (pin "1") (pinfunction "1_1") (pintype "passive"))
    )
    (net (code "50") (name "Net-(D233-A)") (class "Default")
      (node (ref "D233") (pin "1") (pinfunction "A_1") (pintype "passive"))
      (node (ref "S233") (pin "1") (pinfunction "1_1") (pintype "passive"))
    )
    (net (code "51") (name "Net-(D234-A)") (class "Default")
      (node (ref "D234") (pin "1") (pinfunction "A_1") (pintype "passive"))
      (node (ref "S234") (pin "1") (pinfunction "1_1") (pintype "passive"))
    )
    (net (code "52") (name "Net-(D235-A)") (class "Default")
      (node (ref "D235") (pin "1") (pinfunction "A_1") (pintype "passive"))
      (node (ref "S235") (pin "1") (pinfunction "1_1") (pintype "passive"))
    )
    (net (code "53") (name "Net-(D236-A)") (class "Default")
      (node (ref "D236") (pin "1") (pinfunction "A_1") (pintype "passive"))
      (node (ref "S236") (pin "1") (pinfunction "1_1") (pintype "passive"))
    )
    (net (code "54") (name "Net-(D237-A)") (class "Default")
      (node (ref "D237") (pin "1") (pinfunction "A_1") (pintype "passive"))
      (node (ref "S237") (pin "1") (pinfunction "1_1") (pintype "passive"))
    )
    (net (code "55") (name "Net-(D238-A)") (class "Default")
      (node (ref "D238") (pin "1") (pinfunction "A_1") (pintype "passive"))
      (node (ref "S238") (pin "1") (pinfunction "1_1") (pintype "passive"))
    )
    (net (code "56") (name "Net-(D239-A)") (class "Default")
      (node (ref "D239") (pin "1") (pinfunction "A_1") (pintype "passive"))
      (node (ref "S239") (pin "1") (pinfunction "1_1") (pintype "passive"))
    )
    (net (code "57") (name "Net-(D240-A)") (class "Default")
      (node (ref "D240") (pin "1") (pinfunction "A_1") (pintype "passive"))
      (node (ref "S240") (pin "1") (pinfunction "1_1") (pintype "passive"))
    )
    (net (code "58") (name "Net-(D241-A)") (class "Default")
      (node (ref "D241") (pin "1") (pinfunction "A_1") (pintype "passive"))
      (node (ref "S241") (pin "1") (pinfunction "1_1") (pintype "passive"))
    )
    (net (code "59") (name "Net-(D242-A)") (class "Default")
      (node (ref "D242") (pin "1") (pinfunction "A_1") (pintype "passive"))
      (node (ref "S242") (pin "1") (pinfunction "1_1") (pintype "passive"))
    )
    (net (code "60") (name "Net-(D243-A)") (class "Default")
      (node (ref "D243") (pin "1") (pinfunction "A_1") (pintype "passive"))
      (node (ref "S243") (pin "1") (pinfunction "1_1") (pintype "passive"))
    )
    (net (code "61") (name "Net-(D244-A)") (class "Default")
      (node (ref "D244") (pin "1") (pinfunction "A_1") (pintype "passive"))
      (node (ref "S244") (pin "1") (pinfunction "1_1") (pintype "passive"))
    )
    (net (code "62") (name "Net-(D245-A)") (class "Default")
      (node (ref "D245") (pin "1") (pinfunction "A_1") (pintype "passive"))
      (node (ref "S245") (pin "1") (pinfunction "1_1") (pintype "passive"))
    )
    (net (code "63") (name "Net-(D246-A)") (class "Default")
      (node (ref "D246") (pin "1") (pinfunction "A_1") (pintype "passive"))
      (node (ref "S246") (pin "1") (pinfunction "1_1") (pintype "passive"))
    )
    (net (code "64") (name "Net-(D247-A)") (class "Default")
      (node (ref "D247") (pin "1") (pinfunction "A_1") (pintype "passive"))
      (node (ref "S247") (pin "1") (pinfunction "1_1") (pintype "passive"))
    )
    (net (code "65") (name "Net-(D248-A)") (class "Default")
      (node (ref "D248") (pin "1") (pinfunction "A_1") (pintype "passive"))
      (node (ref "S248") (pin "1") (pinfunction "1_1") (pintype "passive"))
    )
    (net (code "66") (name "Net-(D249-A)") (class "Default")
      (node (ref "D249") (pin "1") (pinfunction "A_1") (pintype "passive"))
      (node (ref "S249") (pin "1") (pinfunction "1_1") (pintype "passive"))
    )
    (net (code "67") (name "Net-(D250-A)") (class "Default")
      (node (ref "D250") (pin "1") (pinfunction "A_1") (pintype "passive"))
      (node (ref "S250") (pin "1") (pinfunction "1_1") (pintype "passive"))
    )
    (net (code "68") (name "Net-(D251-A)") (class "Default")
      (node (ref "D251") (pin "1") (pinfunction "A_1") (pintype "passive"))
      (node (ref "S251") (pin "1") (pinfunction "1_1") (pintype "passive"))
    )
    (net (code "69") (name "Net-(D252-A)") (class "Default")
      (node (ref "D252") (pin "1") (pinfunction "A_1") (pintype "passive"))
      (node (ref "S252") (pin "1") (pinfunction "1_1") (pintype "passive"))
    )
    (net (code "70") (name "Net-(D253-A)") (class "Default")
      (node (ref "D253") (pin "1") (pinfunction "A_1") (pintype "passive"))
      (node (ref "S253") (pin "1") (pinfunction "1_1") (pintype "passive"))
    )
    (net (code "71") (name "Net-(D254-A)") (class "Default")
      (node (ref "D254") (pin "1") (pinfunction "A_1") (pintype "passive"))
      (node (ref "S254") (pin "1") (pinfunction "1_1") (pintype "passive"))
    )
    (net (code "72") (name "Net-(D255-A)") (class "Default")
      (node (ref "D255") (pin "1") (pinfunction "A_1") (pintype "passive"))
      (node (ref "S255") (pin "1") (pinfunction "1_1") (pintype "passive"))
    )
    (net (code "73") (name "Net-(D256-A)") (class "Default")
      (node (ref "D256") (pin "1") (pinfunction "A_1") (pintype "passive"))
      (node (ref "S256") (pin "1") (pinfunction "1_1") (pintype "passive"))
    )
    (net (code "74") (name "Net-(D257-A)") (class "Default")
      (node (ref "D257") (pin "1") (pinfunction "A_1") (pintype "passive"))
      (node (ref "S257") (pin "2") (pinfunction "2_2") (pintype "passive"))
    )
    (net (code "75") (name "Net-(D258-A)") (class "Default")
      (node (ref "D258") (pin "1") (pinfunction "A_1") (pintype "passive"))
      (node (ref "S258") (pin "1") (pinfunction "1_1") (pintype "passive"))
    )
    (net (code "76") (name "Net-(D259-A)") (class "Default")
      (node (ref "D259") (pin "1") (pinfunction "A_1") (pintype "passive"))
      (node (ref "S259") (pin "2") (pinfunction "2_2") (pintype "passive"))
    )
    (net (code "77") (name "Net-(D260-A)") (class "Default")
      (node (ref "D260") (pin "1") (pinfunction "A_1") (pintype "passive"))
      (node (ref "S260") (pin "2") (pinfunction "2_2") (pintype "passive"))
    )
    (net (code "78") (name "Net-(D261-A)") (class "Default")
      (node (ref "D261") (pin "1") (pinfunction "A_1") (pintype "passive"))
      (node (ref "S261") (pin "1") (pinfunction "1_1") (pintype "passive"))
    )
    (net (code "79") (name "Net-(D262-A)") (class "Default")
      (node (ref "D262") (pin "1") (pinfunction "A_1") (pintype "passive"))
      (node (ref "S262") (pin "2") (pinfunction "2_2") (pintype "passive"))
    )
    (net (code "80") (name "Net-(D263-A)") (class "Default")
      (node (ref "D263") (pin "1") (pinfunction "A_1") (pintype "passive"))
      (node (ref "S263") (pin "2") (pinfunction "2_2") (pintype "passive"))
    )
    (net (code "81") (name "Net-(D264-A)") (class "Default")
      (node (ref "D264") (pin "1") (pinfunction "A_1") (pintype "passive"))
      (node (ref "S264") (pin "1") (pinfunction "1_1") (pintype "passive"))
    )
    (net (code "82") (name "Net-(D265-A)") (class "Default")
      (node (ref "D265") (pin "1") (pinfunction "A_1") (pintype "passive"))
      (node (ref "S265") (pin "1") (pinfunction "1_1") (pintype "passive"))
    )
    (net (code "83") (name "Net-(D266-A)") (class "Default")
      (node (ref "D266") (pin "1") (pinfunction "A_1") (pintype "passive"))
      (node (ref "S266") (pin "1") (pinfunction "1_1") (pintype "passive"))
    )
    (net (code "84") (name "Net-(D267-A)") (class "Default")
      (node (ref "D267") (pin "1") (pinfunction "A_1") (pintype "passive"))
      (node (ref "S267") (pin "1") (pinfunction "1_1") (pintype "passive"))
    )
    (net (code "85") (name "unconnected-(STAB1-Pad1)") (class "Default")
      (node (ref "STAB1") (pin "1") (pinfunction "1_1") (pintype "passive"))
    )
  )
)
